# M302K.net
KiCad netlist of a schematic drawn in EAGLE
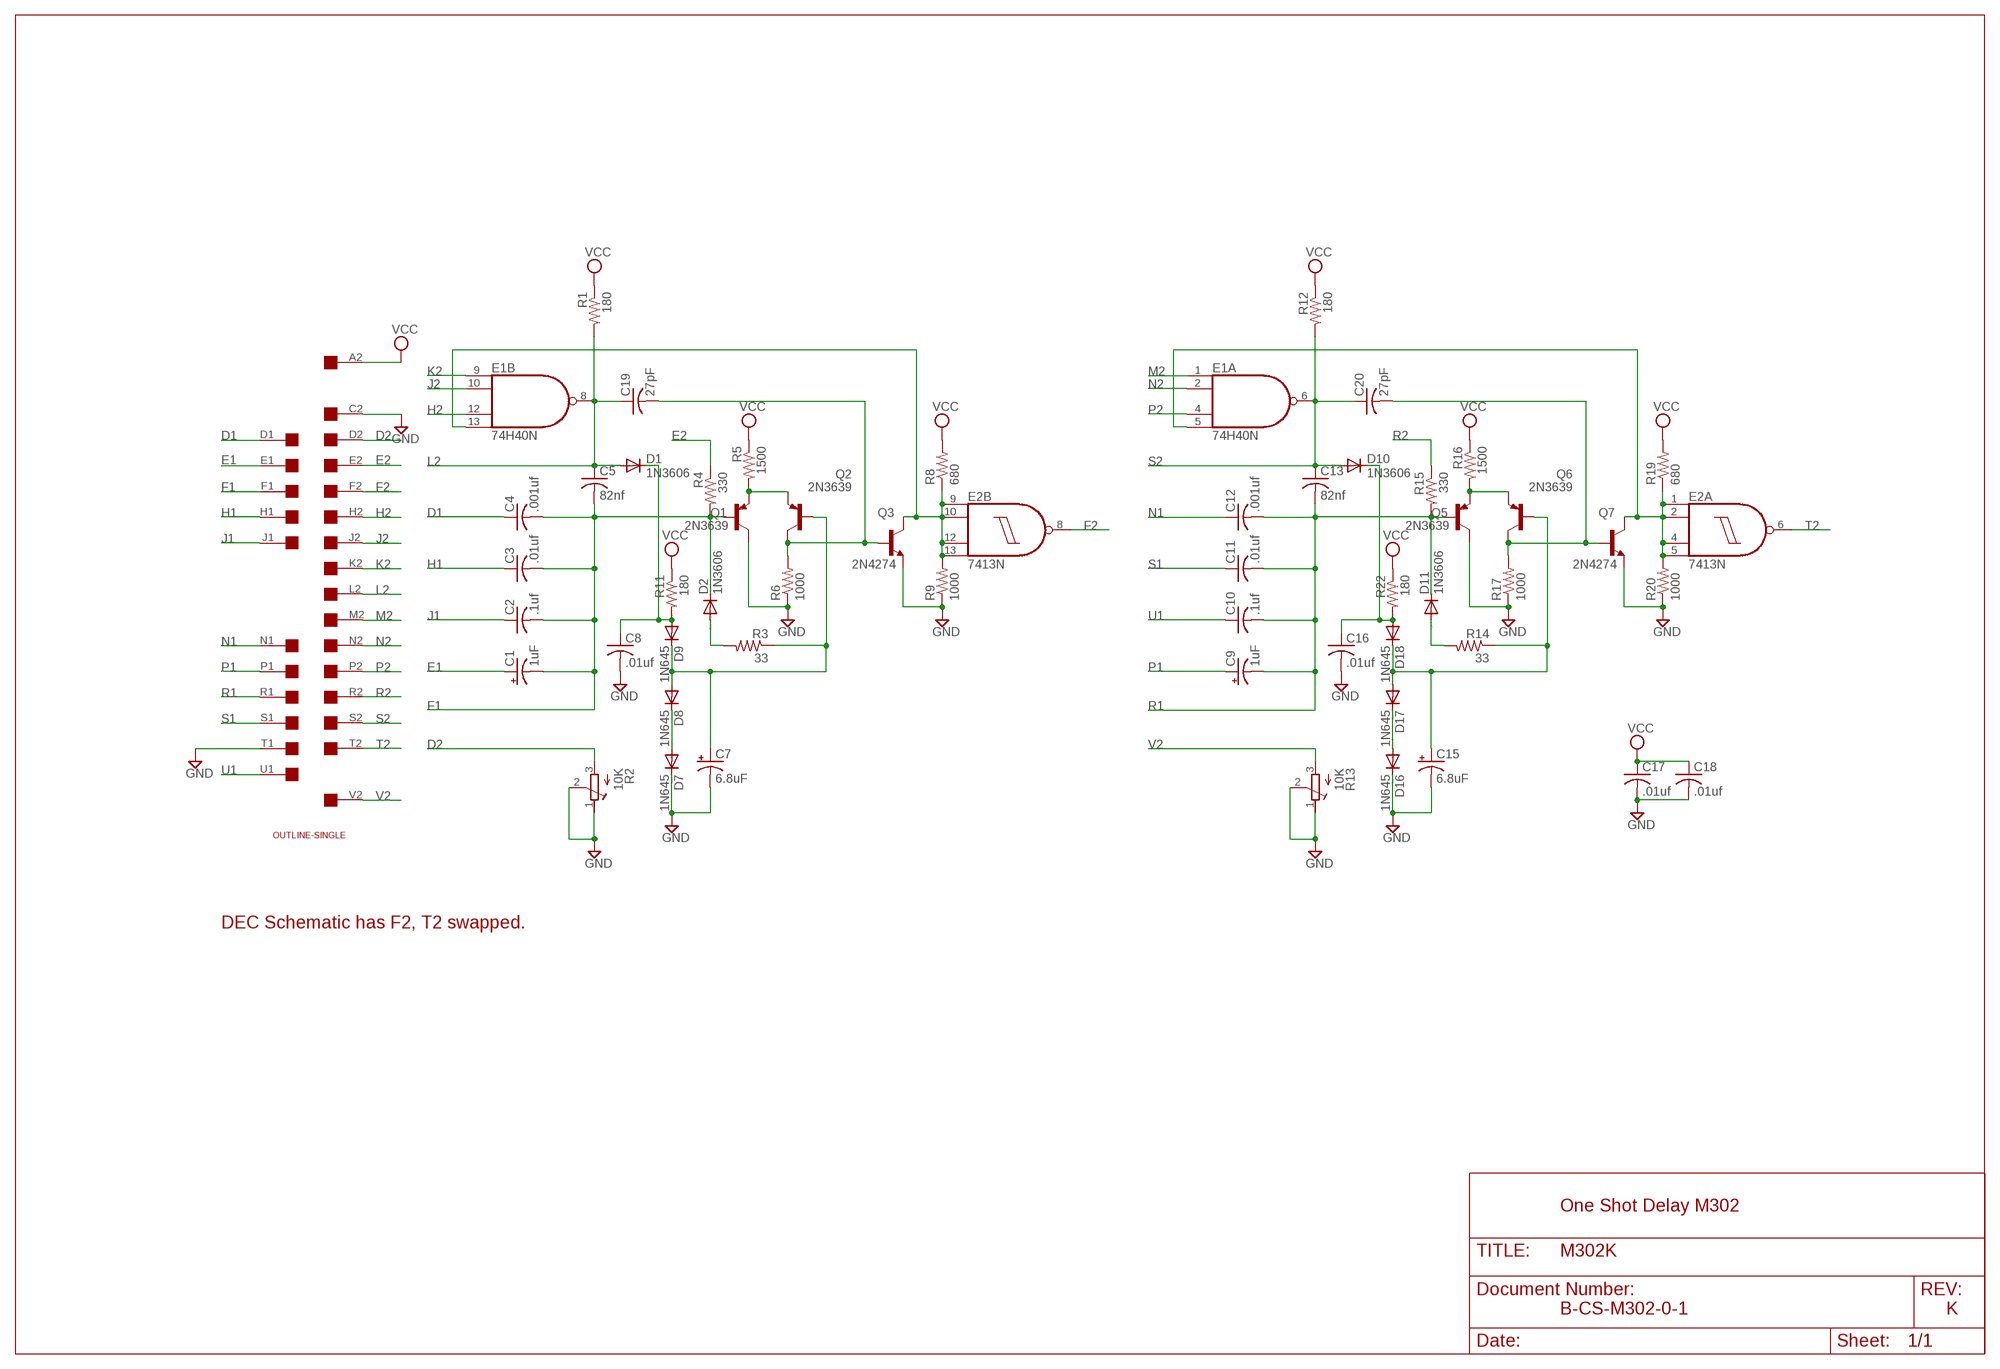
[diagram p0: schematic, sheet 1]

(export (version "E")
  (design (tool "Eeschema 10.0.6"))
  (components
    (comp (ref "C1")
      (value "1uF")
      (footprint "eagle-import:E15-5")
      (libsource (lib "eagle-import") (part "CPOL-USE15-5AXIAL"))
    )
    (comp (ref "C2")
      (value ".1uf")
      (footprint "eagle-import:C275-093X316")
      (libsource (lib "eagle-import") (part "C-US275-093X316"))
    )
    (comp (ref "C3")
      (value ".01uf")
      (footprint "eagle-import:C225-062X268")
      (libsource (lib "eagle-import") (part "C-US225-062X268"))
    )
    (comp (ref "C4")
      (value ".001uf")
      (footprint "eagle-import:C075-032X103")
      (libsource (lib "eagle-import") (part "C-US075-032X103"))
    )
    (comp (ref "C5")
      (value "82nf")
      (footprint "eagle-import:C075-032X103")
      (libsource (lib "eagle-import") (part "C-US075-032X103"))
    )
    (comp (ref "C7")
      (value "6.8uF")
      (footprint "eagle-import:E12-8")
      (libsource (lib "eagle-import") (part "CPOL-USE20-8AXIAL"))
    )
    (comp (ref "C8")
      (value ".01uf")
      (footprint "eagle-import:C050-025X075")
      (libsource (lib "eagle-import") (part "C-US050-025X075"))
    )
    (comp (ref "C9")
      (value "1uF")
      (footprint "eagle-import:E15-5")
      (libsource (lib "eagle-import") (part "CPOL-USE15-5AXIAL"))
    )
    (comp (ref "C10")
      (value ".1uf")
      (footprint "eagle-import:C275-093X316")
      (libsource (lib "eagle-import") (part "C-US275-093X316"))
    )
    (comp (ref "C11")
      (value ".01uf")
      (footprint "eagle-import:C225-062X268")
      (libsource (lib "eagle-import") (part "C-US225-062X268"))
    )
    (comp (ref "C12")
      (value ".001uf")
      (footprint "eagle-import:C075-032X103")
      (libsource (lib "eagle-import") (part "C-US075-032X103"))
    )
    (comp (ref "C13")
      (value "82nf")
      (footprint "eagle-import:C075-032X103")
      (libsource (lib "eagle-import") (part "C-US075-032X103"))
    )
    (comp (ref "C15")
      (value "6.8uF")
      (footprint "eagle-import:E12-8")
      (libsource (lib "eagle-import") (part "CPOL-USE20-8AXIAL"))
    )
    (comp (ref "C16")
      (value ".01uf")
      (footprint "eagle-import:C050-025X075")
      (libsource (lib "eagle-import") (part "C-US050-025X075"))
    )
    (comp (ref "C17")
      (value ".01uf")
      (footprint "eagle-import:C050-025X075")
      (libsource (lib "eagle-import") (part "C-US050-025X075"))
    )
    (comp (ref "C18")
      (value ".01uf")
      (footprint "eagle-import:C050-025X075")
      (libsource (lib "eagle-import") (part "C-US050-025X075"))
    )
    (comp (ref "C19")
      (value "27pF")
      (footprint "eagle-import:C075-032X103")
      (libsource (lib "eagle-import") (part "C-US075-032X103"))
    )
    (comp (ref "C20")
      (value "27pF")
      (footprint "eagle-import:C050-025X075")
      (libsource (lib "eagle-import") (part "C-US050-025X075"))
    )
    (comp (ref "D1")
      (value "1N3606")
      (footprint "eagle-import:DO35-10")
      (libsource (lib "eagle-import") (part "1N4148DO35-10"))
    )
    (comp (ref "D2")
      (value "1N3606")
      (footprint "eagle-import:DO35-10")
      (libsource (lib "eagle-import") (part "1N4148DO35-10"))
    )
    (comp (ref "D7")
      (value "1N645")
      (footprint "eagle-import:DO35-10")
      (libsource (lib "eagle-import") (part "1N4148DO35-10"))
    )
    (comp (ref "D8")
      (value "1N645")
      (footprint "eagle-import:DO35-10")
      (libsource (lib "eagle-import") (part "1N4148DO35-10"))
    )
    (comp (ref "D9")
      (value "1N645")
      (footprint "eagle-import:DO35-10")
      (libsource (lib "eagle-import") (part "1N4148DO35-10"))
    )
    (comp (ref "D10")
      (value "1N3606")
      (footprint "eagle-import:DO35-10")
      (libsource (lib "eagle-import") (part "1N4148DO35-10"))
    )
    (comp (ref "D11")
      (value "1N3606")
      (footprint "eagle-import:DO35-10")
      (libsource (lib "eagle-import") (part "1N4148DO35-10"))
    )
    (comp (ref "D16")
      (value "1N645")
      (footprint "eagle-import:DO35-10")
      (libsource (lib "eagle-import") (part "1N4148DO35-10"))
    )
    (comp (ref "D17")
      (value "1N645")
      (footprint "eagle-import:DO35-10")
      (libsource (lib "eagle-import") (part "1N4148DO35-10"))
    )
    (comp (ref "D18")
      (value "1N645")
      (footprint "eagle-import:DO35-10")
      (libsource (lib "eagle-import") (part "1N4148DO35-10"))
    )
    (comp (ref "E1")
      (value "74H40N")
      (footprint "eagle-import:DIL14")
      (libsource (lib "eagle-import") (part "7420NS"))
    )
    (comp (ref "E2")
      (value "7413N")
      (footprint "eagle-import:DIL14")
      (libsource (lib "eagle-import") (part "7413N"))
    )
    (comp (ref "Q1")
      (value "2N3639")
      (footprint "eagle-import:TO39")
      (libsource (lib "eagle-import") (part "-PNP-TO39-EBC2N3637"))
    )
    (comp (ref "Q2")
      (value "2N3639")
      (footprint "eagle-import:TO39")
      (libsource (lib "eagle-import") (part "-PNP-TO39-EBC2N3637"))
    )
    (comp (ref "Q3")
      (value "2N4274")
      (footprint "eagle-import:TO39")
      (libsource (lib "eagle-import") (part "-NPN-TO39-EBC2N3019"))
    )
    (comp (ref "Q5")
      (value "2N3639")
      (footprint "eagle-import:TO39")
      (libsource (lib "eagle-import") (part "-PNP-TO39-EBC2N3637"))
    )
    (comp (ref "Q6")
      (value "2N3639")
      (footprint "eagle-import:TO39")
      (libsource (lib "eagle-import") (part "-PNP-TO39-EBC2N3637"))
    )
    (comp (ref "Q7")
      (value "2N4274")
      (footprint "eagle-import:TO39")
      (libsource (lib "eagle-import") (part "-NPN-TO39-EBC2N3019"))
    )
    (comp (ref "R1")
      (value "180")
      (footprint "eagle-import:0207_10")
      (libsource (lib "eagle-import") (part "R-US_0207/10"))
    )
    (comp (ref "R2")
      (value "10K")
      (footprint "eagle-import:3006Y")
      (libsource (lib "eagle-import") (part "275P"))
    )
    (comp (ref "R3")
      (value "33")
      (footprint "eagle-import:0207_10")
      (libsource (lib "eagle-import") (part "R-US_0207/10"))
    )
    (comp (ref "R4")
      (value "330")
      (footprint "eagle-import:0207_10")
      (libsource (lib "eagle-import") (part "R-US_0207/10"))
    )
    (comp (ref "R5")
      (value "1500")
      (footprint "eagle-import:0207_10")
      (libsource (lib "eagle-import") (part "R-US_0207/10"))
    )
    (comp (ref "R6")
      (value "1000")
      (footprint "eagle-import:0207_10")
      (libsource (lib "eagle-import") (part "R-US_0207/10"))
    )
    (comp (ref "R8")
      (value "680")
      (footprint "eagle-import:0207_10")
      (libsource (lib "eagle-import") (part "R-US_0207/10"))
    )
    (comp (ref "R9")
      (value "1000")
      (footprint "eagle-import:0207_10")
      (libsource (lib "eagle-import") (part "R-US_0207/10"))
    )
    (comp (ref "R11")
      (value "180")
      (footprint "eagle-import:0207_10")
      (libsource (lib "eagle-import") (part "R-US_0207/10"))
    )
    (comp (ref "R12")
      (value "180")
      (footprint "eagle-import:0207_10")
      (libsource (lib "eagle-import") (part "R-US_0207/10"))
    )
    (comp (ref "R13")
      (value "10K")
      (footprint "eagle-import:3006Y")
      (libsource (lib "eagle-import") (part "275P"))
    )
    (comp (ref "R14")
      (value "33")
      (footprint "eagle-import:0207_10")
      (libsource (lib "eagle-import") (part "R-US_0207/10"))
    )
    (comp (ref "R15")
      (value "330")
      (footprint "eagle-import:0207_10")
      (libsource (lib "eagle-import") (part "R-US_0207/10"))
    )
    (comp (ref "R16")
      (value "1500")
      (footprint "eagle-import:0207_10")
      (libsource (lib "eagle-import") (part "R-US_0207/10"))
    )
    (comp (ref "R17")
      (value "1000")
      (footprint "eagle-import:0207_10")
      (libsource (lib "eagle-import") (part "R-US_0207/10"))
    )
    (comp (ref "R19")
      (value "680")
      (footprint "eagle-import:0207_10")
      (libsource (lib "eagle-import") (part "R-US_0207/10"))
    )
    (comp (ref "R20")
      (value "1000")
      (footprint "eagle-import:0207_10")
      (libsource (lib "eagle-import") (part "R-US_0207/10"))
    )
    (comp (ref "R22")
      (value "180")
      (footprint "eagle-import:0207_10")
      (libsource (lib "eagle-import") (part "R-US_0207/10"))
    )
    (comp (ref "U$1")
      (value "SINGLE")
      (footprint "eagle-import:EDGE-CON2")
      (libsource (lib "eagle-import") (part "SINGLE"))
    )
    (comp (ref "U$2")
      (value "OUTLINE-SINGLE")
      (footprint "eagle-import:SINGLE")
      (libsource (lib "eagle-import") (part "OUTLINE-SINGLE"))
    )
  )
  (nets
    (net (code "1") (name "/D1") (class "Default")
      (node (ref "C4") (pin "1") (pinfunction "1_1") (pintype "passive"))
      (node (ref "U$1") (pin "D1") (pinfunction "1_D1") (pintype "bidirectional"))
    )
    (net (code "2") (name "/D2") (class "Default")
      (node (ref "R2") (pin "3") (pinfunction "E_3") (pintype "passive"))
      (node (ref "U$1") (pin "D2") (pinfunction "1_D2") (pintype "bidirectional"))
    )
    (net (code "3") (name "/E1") (class "Default")
      (node (ref "C1") (pin "+") (pinfunction "+_+") (pintype "passive"))
      (node (ref "U$1") (pin "E1") (pinfunction "1_E1") (pintype "bidirectional"))
    )
    (net (code "4") (name "/E2") (class "Default")
      (node (ref "R4") (pin "1") (pinfunction "1_1") (pintype "passive"))
      (node (ref "U$1") (pin "E2") (pinfunction "1_E2") (pintype "bidirectional"))
    )
    (net (code "5") (name "/F1") (class "Default")
      (node (ref "C1") (pin "-") (pinfunction "-_-") (pintype "passive"))
      (node (ref "C2") (pin "2") (pinfunction "2_2") (pintype "passive"))
      (node (ref "C3") (pin "2") (pinfunction "2_2") (pintype "passive"))
      (node (ref "C4") (pin "2") (pinfunction "2_2") (pintype "passive"))
      (node (ref "C5") (pin "2") (pinfunction "2_2") (pintype "passive"))
      (node (ref "D2") (pin "C") (pinfunction "C_C") (pintype "passive"))
      (node (ref "Q1") (pin "2") (pinfunction "B_2") (pintype "passive"))
      (node (ref "R4") (pin "2") (pinfunction "2_2") (pintype "passive"))
      (node (ref "U$1") (pin "F1") (pinfunction "1_F1") (pintype "bidirectional"))
    )
    (net (code "6") (name "/F2") (class "Default")
      (node (ref "E2") (pin "8") (pinfunction "O_8") (pintype "output"))
      (node (ref "U$1") (pin "F2") (pinfunction "1_F2") (pintype "bidirectional"))
    )
    (net (code "7") (name "/H1") (class "Default")
      (node (ref "C3") (pin "1") (pinfunction "1_1") (pintype "passive"))
      (node (ref "U$1") (pin "H1") (pinfunction "1_H1") (pintype "bidirectional"))
    )
    (net (code "8") (name "/H2") (class "Default")
      (node (ref "E1") (pin "12") (pinfunction "I2_12") (pintype "input"))
      (node (ref "U$1") (pin "H2") (pinfunction "1_H2") (pintype "bidirectional"))
    )
    (net (code "9") (name "/J1") (class "Default")
      (node (ref "C2") (pin "1") (pinfunction "1_1") (pintype "passive"))
      (node (ref "U$1") (pin "J1") (pinfunction "1_J1") (pintype "bidirectional"))
    )
    (net (code "10") (name "/J2") (class "Default")
      (node (ref "E1") (pin "10") (pinfunction "I1_10") (pintype "input"))
      (node (ref "U$1") (pin "J2") (pinfunction "1_J2") (pintype "bidirectional"))
    )
    (net (code "11") (name "/K2") (class "Default")
      (node (ref "E1") (pin "9") (pinfunction "I0_9") (pintype "input"))
      (node (ref "U$1") (pin "K2") (pinfunction "1_K2") (pintype "bidirectional"))
    )
    (net (code "12") (name "/L2") (class "Default")
      (node (ref "C19") (pin "1") (pinfunction "1_1") (pintype "passive"))
      (node (ref "C5") (pin "1") (pinfunction "1_1") (pintype "passive"))
      (node (ref "D1") (pin "A") (pinfunction "A_A") (pintype "passive"))
      (node (ref "E1") (pin "8") (pinfunction "O_8") (pintype "output"))
      (node (ref "R1") (pin "2") (pinfunction "2_2") (pintype "passive"))
      (node (ref "U$1") (pin "L2") (pinfunction "1_L2") (pintype "bidirectional"))
    )
    (net (code "13") (name "/M2") (class "Default")
      (node (ref "E1") (pin "1") (pinfunction "I0_1") (pintype "input"))
      (node (ref "U$1") (pin "M2") (pinfunction "1_M2") (pintype "bidirectional"))
    )
    (net (code "14") (name "/N1") (class "Default")
      (node (ref "C12") (pin "1") (pinfunction "1_1") (pintype "passive"))
      (node (ref "U$1") (pin "N1") (pinfunction "1_N1") (pintype "bidirectional"))
    )
    (net (code "15") (name "/N2") (class "Default")
      (node (ref "E1") (pin "2") (pinfunction "I1_2") (pintype "input"))
      (node (ref "U$1") (pin "N2") (pinfunction "1_N2") (pintype "bidirectional"))
    )
    (net (code "16") (name "/P1") (class "Default")
      (node (ref "C9") (pin "+") (pinfunction "+_+") (pintype "passive"))
      (node (ref "U$1") (pin "P1") (pinfunction "1_P1") (pintype "bidirectional"))
    )
    (net (code "17") (name "/P2") (class "Default")
      (node (ref "E1") (pin "4") (pinfunction "I2_4") (pintype "input"))
      (node (ref "U$1") (pin "P2") (pinfunction "1_P2") (pintype "bidirectional"))
    )
    (net (code "18") (name "/R1") (class "Default")
      (node (ref "C10") (pin "2") (pinfunction "2_2") (pintype "passive"))
      (node (ref "C11") (pin "2") (pinfunction "2_2") (pintype "passive"))
      (node (ref "C12") (pin "2") (pinfunction "2_2") (pintype "passive"))
      (node (ref "C13") (pin "2") (pinfunction "2_2") (pintype "passive"))
      (node (ref "C9") (pin "-") (pinfunction "-_-") (pintype "passive"))
      (node (ref "D11") (pin "C") (pinfunction "C_C") (pintype "passive"))
      (node (ref "Q5") (pin "2") (pinfunction "B_2") (pintype "passive"))
      (node (ref "R15") (pin "2") (pinfunction "2_2") (pintype "passive"))
      (node (ref "U$1") (pin "R1") (pinfunction "1_R1") (pintype "bidirectional"))
    )
    (net (code "19") (name "/R2") (class "Default")
      (node (ref "R15") (pin "1") (pinfunction "1_1") (pintype "passive"))
      (node (ref "U$1") (pin "R2") (pinfunction "1_R2") (pintype "bidirectional"))
    )
    (net (code "20") (name "/S1") (class "Default")
      (node (ref "C11") (pin "1") (pinfunction "1_1") (pintype "passive"))
      (node (ref "U$1") (pin "S1") (pinfunction "1_S1") (pintype "bidirectional"))
    )
    (net (code "21") (name "/S2") (class "Default")
      (node (ref "C13") (pin "1") (pinfunction "1_1") (pintype "passive"))
      (node (ref "C20") (pin "1") (pinfunction "1_1") (pintype "passive"))
      (node (ref "D10") (pin "A") (pinfunction "A_A") (pintype "passive"))
      (node (ref "E1") (pin "6") (pinfunction "O_6") (pintype "output"))
      (node (ref "R12") (pin "2") (pinfunction "2_2") (pintype "passive"))
      (node (ref "U$1") (pin "S2") (pinfunction "1_S2") (pintype "bidirectional"))
    )
    (net (code "22") (name "/T2") (class "Default")
      (node (ref "E2") (pin "6") (pinfunction "O_6") (pintype "output"))
      (node (ref "U$1") (pin "T2") (pinfunction "1_T2") (pintype "bidirectional"))
    )
    (net (code "23") (name "/U1") (class "Default")
      (node (ref "C10") (pin "1") (pinfunction "1_1") (pintype "passive"))
      (node (ref "U$1") (pin "U1") (pinfunction "1_U1") (pintype "bidirectional"))
    )
    (net (code "24") (name "/V2") (class "Default")
      (node (ref "R13") (pin "3") (pinfunction "E_3") (pintype "passive"))
      (node (ref "U$1") (pin "V2") (pinfunction "1_V2") (pintype "bidirectional"))
    )
    (net (code "25") (name "GND") (class "Default")
      (node (ref "C15") (pin "-") (pinfunction "-_-") (pintype "passive"))
      (node (ref "C16") (pin "2") (pinfunction "2_2") (pintype "passive"))
      (node (ref "C17") (pin "2") (pinfunction "2_2") (pintype "passive"))
      (node (ref "C18") (pin "2") (pinfunction "2_2") (pintype "passive"))
      (node (ref "C7") (pin "-") (pinfunction "-_-") (pintype "passive"))
      (node (ref "C8") (pin "2") (pinfunction "2_2") (pintype "passive"))
      (node (ref "D16") (pin "C") (pinfunction "C_C") (pintype "passive"))
      (node (ref "D7") (pin "C") (pinfunction "C_C") (pintype "passive"))
      (node (ref "Q1") (pin "3") (pinfunction "C_3") (pintype "passive"))
      (node (ref "Q3") (pin "1") (pinfunction "E_1") (pintype "passive"))
      (node (ref "Q5") (pin "3") (pinfunction "C_3") (pintype "passive"))
      (node (ref "Q7") (pin "1") (pinfunction "E_1") (pintype "passive"))
      (node (ref "R13") (pin "1") (pinfunction "A_1") (pintype "passive"))
      (node (ref "R13") (pin "2") (pinfunction "S_2") (pintype "passive"))
      (node (ref "R17") (pin "1") (pinfunction "1_1") (pintype "passive"))
      (node (ref "R2") (pin "1") (pinfunction "A_1") (pintype "passive"))
      (node (ref "R2") (pin "2") (pinfunction "S_2") (pintype "passive"))
      (node (ref "R20") (pin "1") (pinfunction "1_1") (pintype "passive"))
      (node (ref "R6") (pin "1") (pinfunction "1_1") (pintype "passive"))
      (node (ref "R9") (pin "1") (pinfunction "1_1") (pintype "passive"))
      (node (ref "U$1") (pin "C2") (pinfunction "1_C2") (pintype "bidirectional"))
      (node (ref "U$1") (pin "T1") (pinfunction "1_T1") (pintype "bidirectional"))
    )
    (net (code "26") (name "Net-(C8-Pad1)") (class "Default")
      (node (ref "C8") (pin "1") (pinfunction "1_1") (pintype "passive"))
      (node (ref "D1") (pin "C") (pinfunction "C_C") (pintype "passive"))
      (node (ref "D9") (pin "A") (pinfunction "A_A") (pintype "passive"))
      (node (ref "R11") (pin "2") (pinfunction "2_2") (pintype "passive"))
    )
    (net (code "27") (name "Net-(C16-Pad1)") (class "Default")
      (node (ref "C16") (pin "1") (pinfunction "1_1") (pintype "passive"))
      (node (ref "D10") (pin "C") (pinfunction "C_C") (pintype "passive"))
      (node (ref "D18") (pin "A") (pinfunction "A_A") (pintype "passive"))
      (node (ref "R22") (pin "2") (pinfunction "2_2") (pintype "passive"))
    )
    (net (code "28") (name "Net-(D2-PadA)") (class "Default")
      (node (ref "D2") (pin "A") (pinfunction "A_A") (pintype "passive"))
      (node (ref "R3") (pin "2") (pinfunction "2_2") (pintype "passive"))
    )
    (net (code "29") (name "Net-(D7-PadA)") (class "Default")
      (node (ref "D7") (pin "A") (pinfunction "A_A") (pintype "passive"))
      (node (ref "D8") (pin "C") (pinfunction "C_C") (pintype "passive"))
    )
    (net (code "30") (name "Net-(D11-PadA)") (class "Default")
      (node (ref "D11") (pin "A") (pinfunction "A_A") (pintype "passive"))
      (node (ref "R14") (pin "2") (pinfunction "2_2") (pintype "passive"))
    )
    (net (code "31") (name "Net-(D16-PadA)") (class "Default")
      (node (ref "D16") (pin "A") (pinfunction "A_A") (pintype "passive"))
      (node (ref "D17") (pin "C") (pinfunction "C_C") (pintype "passive"))
    )
    (net (code "32") (name "Net-(E1A-I3)") (class "Default")
      (node (ref "E1") (pin "5") (pinfunction "I3_5") (pintype "input"))
      (node (ref "E2") (pin "1") (pinfunction "I0_1") (pintype "input"))
      (node (ref "E2") (pin "2") (pinfunction "I1_2") (pintype "input"))
      (node (ref "E2") (pin "4") (pinfunction "I2_4") (pintype "input"))
      (node (ref "E2") (pin "5") (pinfunction "I3_5") (pintype "input"))
      (node (ref "Q7") (pin "3") (pinfunction "C_3") (pintype "passive"))
      (node (ref "R19") (pin "1") (pinfunction "1_1") (pintype "passive"))
      (node (ref "R20") (pin "2") (pinfunction "2_2") (pintype "passive"))
    )
    (net (code "33") (name "Net-(E1B-I3)") (class "Default")
      (node (ref "E1") (pin "13") (pinfunction "I3_13") (pintype "input"))
      (node (ref "E2") (pin "10") (pinfunction "I1_10") (pintype "input"))
      (node (ref "E2") (pin "12") (pinfunction "I2_12") (pintype "input"))
      (node (ref "E2") (pin "13") (pinfunction "I3_13") (pintype "input"))
      (node (ref "E2") (pin "9") (pinfunction "I0_9") (pintype "input"))
      (node (ref "Q3") (pin "3") (pinfunction "C_3") (pintype "passive"))
      (node (ref "R8") (pin "1") (pinfunction "1_1") (pintype "passive"))
      (node (ref "R9") (pin "2") (pinfunction "2_2") (pintype "passive"))
    )
    (net (code "34") (name "Net-(Q1-E)") (class "Default")
      (node (ref "Q1") (pin "1") (pinfunction "E_1") (pintype "passive"))
      (node (ref "Q2") (pin "1") (pinfunction "E_1") (pintype "passive"))
      (node (ref "R5") (pin "2") (pinfunction "2_2") (pintype "passive"))
    )
    (net (code "35") (name "Net-(Q2-B)") (class "Default")
      (node (ref "C7") (pin "+") (pinfunction "+_+") (pintype "passive"))
      (node (ref "D8") (pin "A") (pinfunction "A_A") (pintype "passive"))
      (node (ref "D9") (pin "C") (pinfunction "C_C") (pintype "passive"))
      (node (ref "Q2") (pin "2") (pinfunction "B_2") (pintype "passive"))
      (node (ref "R3") (pin "1") (pinfunction "1_1") (pintype "passive"))
    )
    (net (code "36") (name "Net-(Q2-C)") (class "Default")
      (node (ref "C19") (pin "2") (pinfunction "2_2") (pintype "passive"))
      (node (ref "Q2") (pin "3") (pinfunction "C_3") (pintype "passive"))
      (node (ref "Q3") (pin "2") (pinfunction "B_2") (pintype "passive"))
      (node (ref "R6") (pin "2") (pinfunction "2_2") (pintype "passive"))
    )
    (net (code "37") (name "Net-(Q5-E)") (class "Default")
      (node (ref "Q5") (pin "1") (pinfunction "E_1") (pintype "passive"))
      (node (ref "Q6") (pin "1") (pinfunction "E_1") (pintype "passive"))
      (node (ref "R16") (pin "2") (pinfunction "2_2") (pintype "passive"))
    )
    (net (code "38") (name "Net-(Q6-B)") (class "Default")
      (node (ref "C15") (pin "+") (pinfunction "+_+") (pintype "passive"))
      (node (ref "D17") (pin "A") (pinfunction "A_A") (pintype "passive"))
      (node (ref "D18") (pin "C") (pinfunction "C_C") (pintype "passive"))
      (node (ref "Q6") (pin "2") (pinfunction "B_2") (pintype "passive"))
      (node (ref "R14") (pin "1") (pinfunction "1_1") (pintype "passive"))
    )
    (net (code "39") (name "Net-(Q6-C)") (class "Default")
      (node (ref "C20") (pin "2") (pinfunction "2_2") (pintype "passive"))
      (node (ref "Q6") (pin "3") (pinfunction "C_3") (pintype "passive"))
      (node (ref "Q7") (pin "2") (pinfunction "B_2") (pintype "passive"))
      (node (ref "R17") (pin "2") (pinfunction "2_2") (pintype "passive"))
    )
    (net (code "40") (name "VCC") (class "Default")
      (node (ref "C17") (pin "1") (pinfunction "1_1") (pintype "passive"))
      (node (ref "C18") (pin "1") (pinfunction "1_1") (pintype "passive"))
      (node (ref "R1") (pin "1") (pinfunction "1_1") (pintype "passive"))
      (node (ref "R11") (pin "1") (pinfunction "1_1") (pintype "passive"))
      (node (ref "R12") (pin "1") (pinfunction "1_1") (pintype "passive"))
      (node (ref "R16") (pin "1") (pinfunction "1_1") (pintype "passive"))
      (node (ref "R19") (pin "2") (pinfunction "2_2") (pintype "passive"))
      (node (ref "R22") (pin "1") (pinfunction "1_1") (pintype "passive"))
      (node (ref "R5") (pin "1") (pinfunction "1_1") (pintype "passive"))
      (node (ref "R8") (pin "2") (pinfunction "2_2") (pintype "passive"))
      (node (ref "U$1") (pin "A2") (pinfunction "1_A2") (pintype "bidirectional"))
    )
  )
)
